# BTTC.net
KiCad netlist of a schematic drawn in Altium Designer
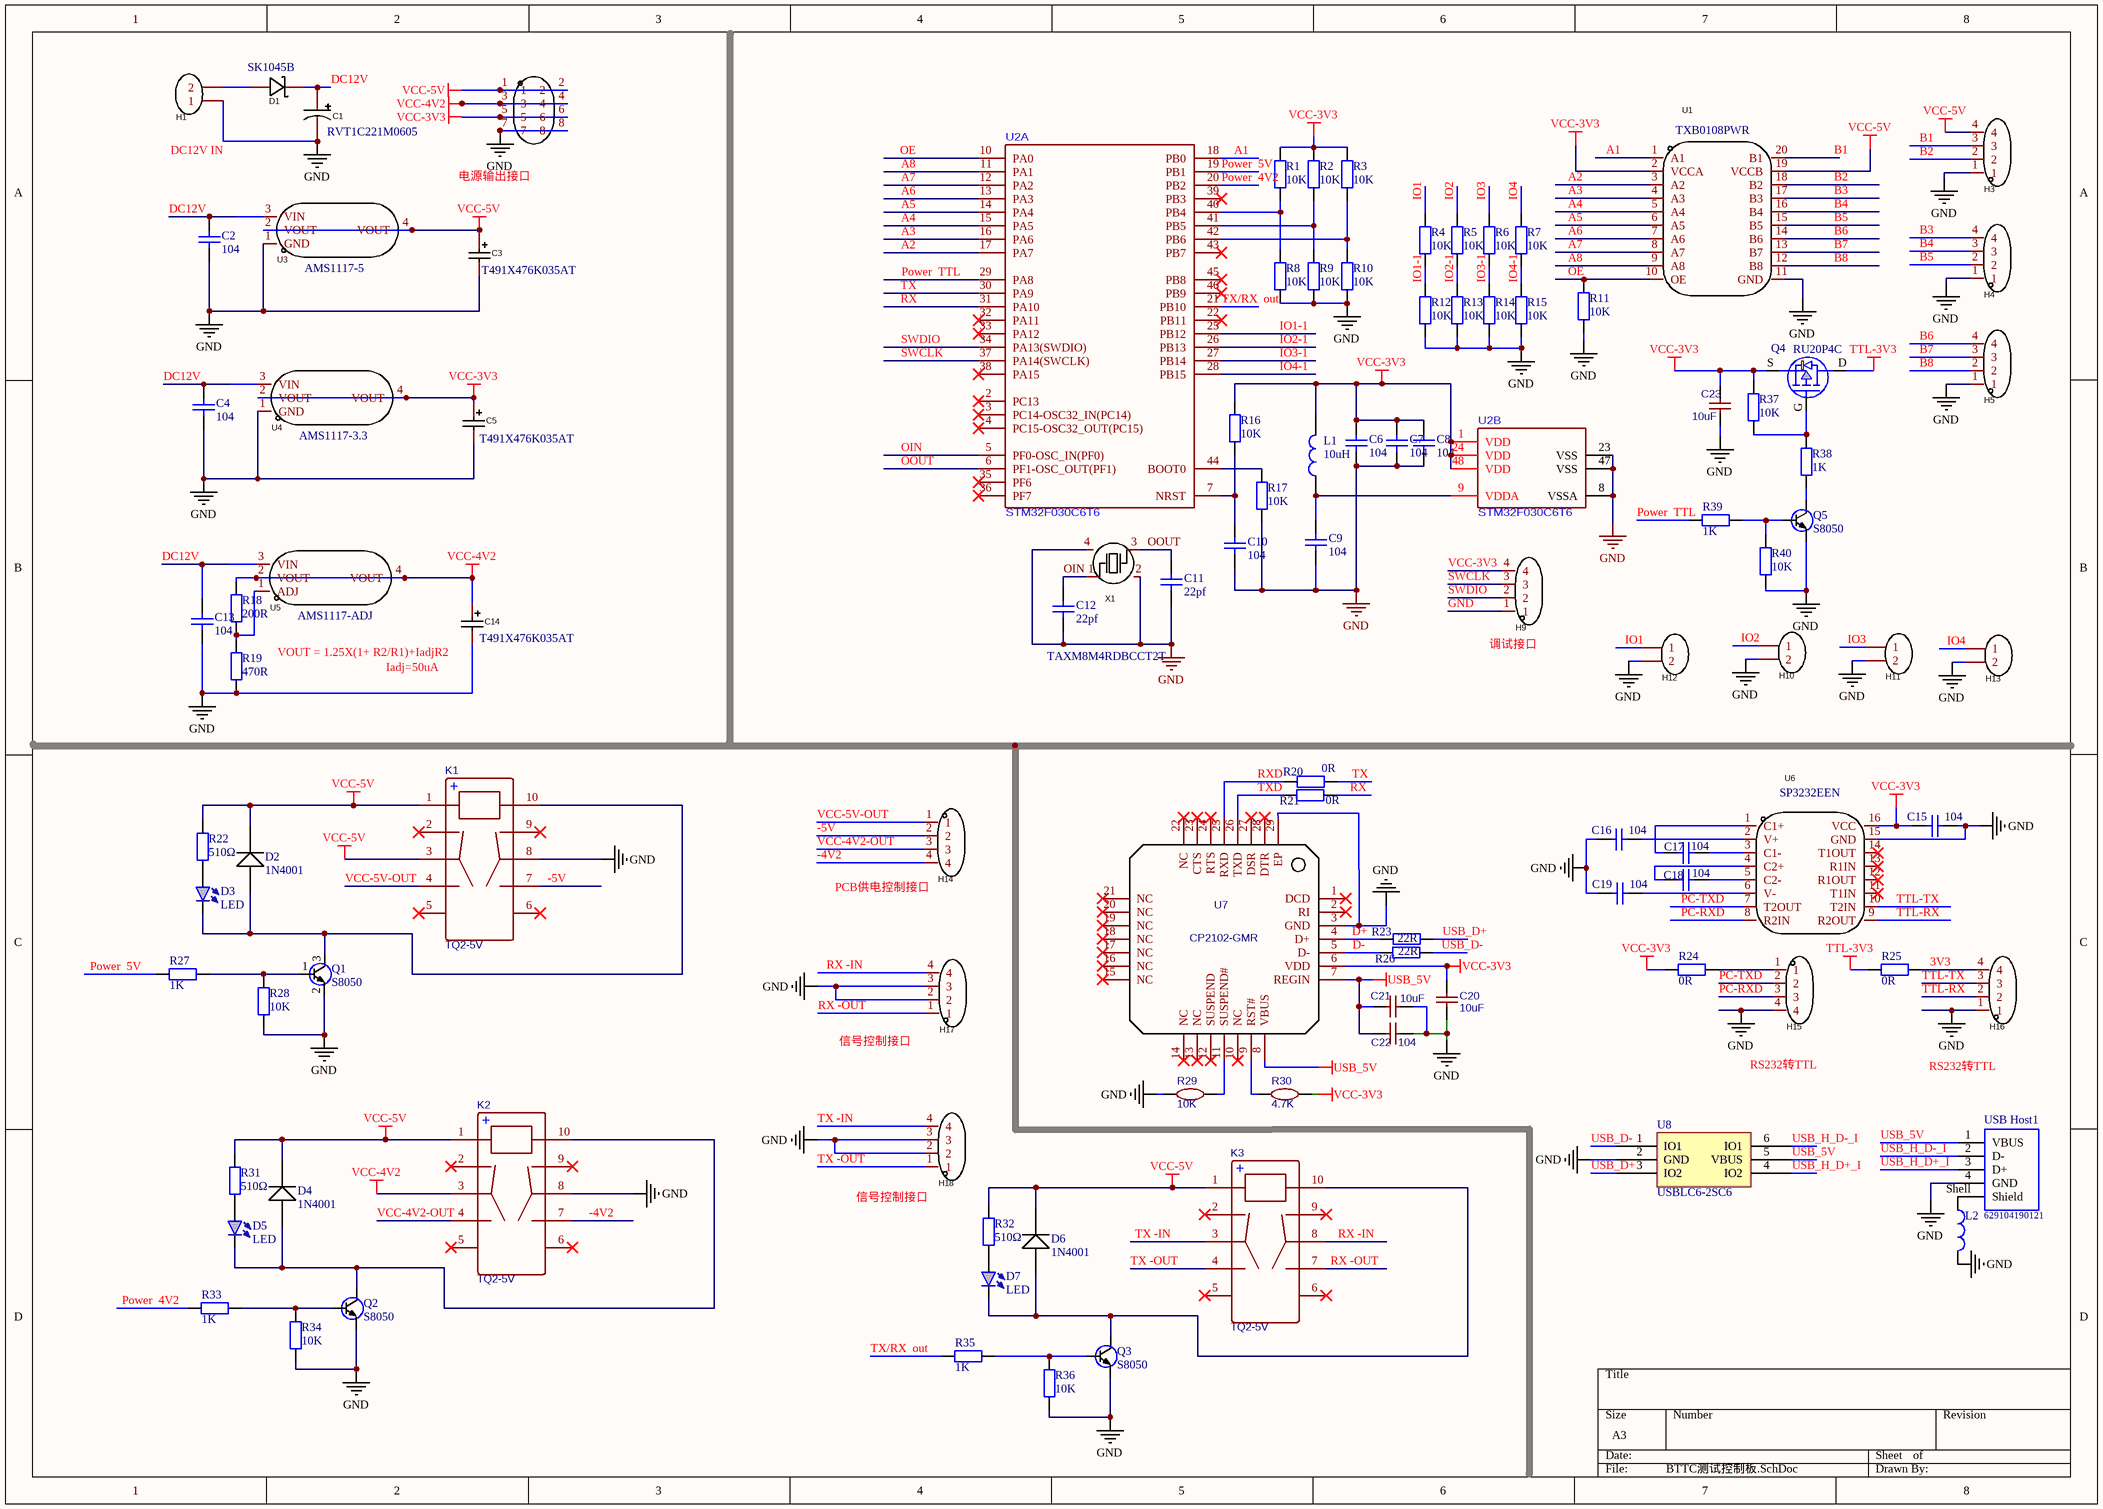
[diagram p0: BTTC测试控制板.SchDoc]

(export (version "E")
  (design (tool "Eeschema 10.0.6"))
  (components
    (comp (ref "C1")
      (value "RVT1C221M0605")
      (footprint "CAP-SMD_BD10.0-L10.3-W10.3-LS11.0-FD")
      (fields (field (name "MANUFACTURER") "ROQANG(容强)") (field (name "TOLERANCE") "±20%"))
      (libsource (lib "SNOWFLAKEV1.0") (part "RVT1C221M0605"))
    )
    (comp (ref "C2") (value "104") (footprint "C0603") (libsource (lib "SNOWFLAKEV1.0") (part "CAP")))
    (comp (ref "C3")
      (value "T491X476K035AT")
      (footprint "CAP-SMD_L3.5-W2.8-R-RD")
      (libsource (lib "altium-import") (part "root_3_T491X476K035AT_"))
    )
    (comp (ref "C4") (value "104") (footprint "C0603") (libsource (lib "SNOWFLAKEV1.0") (part "CAP")))
    (comp (ref "C5")
      (value "T491X476K035AT")
      (footprint "CAP-SMD_L3.5-W2.8-R-RD")
      (libsource (lib "altium-import") (part "root_3_T491X476K035AT_"))
    )
    (comp (ref "C6") (value "104") (footprint "C0603") (libsource (lib "SNOWFLAKEV1.0") (part "CAP")))
    (comp (ref "C7") (value "104") (footprint "C0603") (libsource (lib "SNOWFLAKEV1.0") (part "CAP")))
    (comp (ref "C8") (value "104") (footprint "C0603") (libsource (lib "SNOWFLAKEV1.0") (part "CAP")))
    (comp (ref "C9") (value "104") (footprint "C0603") (libsource (lib "SNOWFLAKEV1.0") (part "CAP")))
    (comp (ref "C10") (value "104") (footprint "C0603") (libsource (lib "SNOWFLAKEV1.0") (part "CAP")))
    (comp (ref "C11") (value "22pf") (footprint "C0603") (libsource (lib "SNOWFLAKEV1.0") (part "CAP")))
    (comp (ref "C12") (value "22pf") (footprint "C0603") (libsource (lib "SNOWFLAKEV1.0") (part "CAP")))
    (comp (ref "C13") (value "104") (footprint "C0603") (libsource (lib "SNOWFLAKEV1.0") (part "CAP")))
    (comp (ref "C14")
      (value "T491X476K035AT")
      (footprint "CAP-SMD_L3.5-W2.8-R-RD")
      (libsource (lib "altium-import") (part "root_3_T491X476K035AT_"))
    )
    (comp (ref "C15") (value "104") (footprint "C0603") (libsource (lib "SNOWFLAKEV1.0") (part "CAP")))
    (comp (ref "C16") (value "104") (footprint "C0603") (libsource (lib "SNOWFLAKEV1.0") (part "CAP")))
    (comp (ref "C17") (value "104") (footprint "C0603") (libsource (lib "SNOWFLAKEV1.0") (part "CAP")))
    (comp (ref "C18") (value "104") (footprint "C0603") (libsource (lib "SNOWFLAKEV1.0") (part "CAP")))
    (comp (ref "C19") (value "104") (footprint "C0603") (libsource (lib "SNOWFLAKEV1.0") (part "CAP")))
    (comp (ref "C20")
      (value "10uF")
      (footprint "C0603")
      (fields
        (field (name "BOM_MANUFACTURER PART") "0603X106K100NT")
        (field (name "BOM_SUPPLIER PART") "C38898")
      )
      (libsource (lib "altium-import") (part "root_1_mirrored_10uF_"))
    )
    (comp (ref "C21")
      (value "10uF")
      (footprint "C0603")
      (fields
        (field (name "BOM_MANUFACTURER PART") "0603X106K100NT")
        (field (name "BOM_SUPPLIER PART") "C38898")
      )
      (libsource (lib "altium-import") (part "root_2_mirrored_10uF_"))
    )
    (comp (ref "C22")
      (value "104")
      (footprint "C0603")
      (fields
        (field (name "BOM_MANUFACTURER PART") "0603B104K500NT")
        (field (name "BOM_SUPPLIER PART") "C30926")
      )
      (libsource (lib "altium-import") (part "root_2_mirrored_100nF_"))
    )
    (comp (ref "C23")
      (value "10uF")
      (footprint "C0603")
      (fields
        (field (name "BOM_MANUFACTURER PART") "0603X106K100NT")
        (field (name "BOM_SUPPLIER PART") "C38898")
      )
      (libsource (lib "altium-import") (part "root_3_mirrored_10uF_"))
    )
    (comp (ref "D1")
      (value "SK1045B")
      (footprint "SMB_L4.6-W3.6-LS5.3-RD")
      (fields (field (name "MANUFACTURER") "MDD"))
      (libsource (lib "SNOWFLAKEV1.0") (part "SK1045B"))
    )
    (comp (ref "D2")
      (value "1N4001")
      (footprint "SMB_L4.6-W3.6-LS5.3-RD")
      (libsource (lib "Schlib2") (part "D"))
    )
    (comp (ref "D3")
      (value "LED")
      (footprint "LED_0603")
      (description "贴片电阻")
      (libsource (lib "SelfbulitSCH_library") (part "LED"))
    )
    (comp (ref "D4")
      (value "1N4001")
      (footprint "SMB_L4.6-W3.6-LS5.3-RD")
      (libsource (lib "Schlib2") (part "D"))
    )
    (comp (ref "D5")
      (value "LED")
      (footprint "LED_0603")
      (description "贴片电阻")
      (libsource (lib "SelfbulitSCH_library") (part "LED"))
    )
    (comp (ref "D6")
      (value "1N4001")
      (footprint "SMB_L4.6-W3.6-LS5.3-RD")
      (libsource (lib "Schlib2") (part "D"))
    )
    (comp (ref "D7")
      (value "LED")
      (footprint "LED_0603")
      (description "贴片电阻")
      (libsource (lib "SelfbulitSCH_library") (part "LED"))
    )
    (comp (ref "H1")
      (value "2P")
      (footprint "CONN-TH_2P-P2.54")
      (fields
        (field (name "MANUFACTURER") "TE Connectivity(美国泰科)")
        (field (name "MANUFACTURER PART") "826629-2")
      )
      (libsource (lib "BTT测试控制板") (part "2P"))
    )
    (comp (ref "H2")
      (value "8p-2.54")
      (footprint "P2.54-4X2")
      (fields
        (field (name "MANUFACTURER") "TE Connectivity(美国泰科)")
        (field (name "MANUFACTURER PART") "826629-4")
      )
      (libsource (lib "BTT测试控制板") (part "8p-2.54"))
    )
    (comp (ref "H3")
      (value "4p-2.54")
      (footprint "CONN-TH_4P-P2.54")
      (fields
        (field (name "MANUFACTURER") "TE Connectivity(美国泰科)")
        (field (name "MANUFACTURER PART") "826629-4")
      )
      (libsource (lib "SNOWFLAKEV1.0") (part "4p-2.54"))
    )
    (comp (ref "H4")
      (value "4p-2.54")
      (footprint "CONN-TH_4P-P2.54")
      (fields
        (field (name "MANUFACTURER") "TE Connectivity(美国泰科)")
        (field (name "MANUFACTURER PART") "826629-4")
      )
      (libsource (lib "SNOWFLAKEV1.0") (part "4p-2.54"))
    )
    (comp (ref "H5")
      (value "4p-2.54")
      (footprint "CONN-TH_4P-P2.54")
      (fields
        (field (name "MANUFACTURER") "TE Connectivity(美国泰科)")
        (field (name "MANUFACTURER PART") "826629-4")
      )
      (libsource (lib "SNOWFLAKEV1.0") (part "4p-2.54"))
    )
    (comp (ref "H9")
      (value "4p-2.54")
      (footprint "CONN-TH_4P-P2.54")
      (fields
        (field (name "MANUFACTURER") "TE Connectivity(美国泰科)")
        (field (name "MANUFACTURER PART") "826629-4")
      )
      (libsource (lib "SNOWFLAKEV1.0") (part "4p-2.54"))
    )
    (comp (ref "H10")
      (value "2P")
      (footprint "CONN-TH_2P-P2.54")
      (fields
        (field (name "MANUFACTURER") "TE Connectivity(美国泰科)")
        (field (name "MANUFACTURER PART") "826629-2")
      )
      (libsource (lib "BTT测试控制板") (part "2P"))
    )
    (comp (ref "H11")
      (value "2P")
      (footprint "CONN-TH_2P-P2.54")
      (fields
        (field (name "MANUFACTURER") "TE Connectivity(美国泰科)")
        (field (name "MANUFACTURER PART") "826629-2")
      )
      (libsource (lib "BTT测试控制板") (part "2P"))
    )
    (comp (ref "H12")
      (value "2P")
      (footprint "CONN-TH_2P-P2.54")
      (fields
        (field (name "MANUFACTURER") "TE Connectivity(美国泰科)")
        (field (name "MANUFACTURER PART") "826629-2")
      )
      (libsource (lib "BTT测试控制板") (part "2P"))
    )
    (comp (ref "H13")
      (value "2P")
      (footprint "CONN-TH_2P-P2.54")
      (fields
        (field (name "MANUFACTURER") "TE Connectivity(美国泰科)")
        (field (name "MANUFACTURER PART") "826629-2")
      )
      (libsource (lib "BTT测试控制板") (part "2P"))
    )
    (comp (ref "H14")
      (value "4p-2.54")
      (footprint "CONN-TH_4P-P2.54")
      (fields
        (field (name "MANUFACTURER") "TE Connectivity(美国泰科)")
        (field (name "MANUFACTURER PART") "826629-4")
      )
      (libsource (lib "SNOWFLAKEV1.0") (part "4p-2.54"))
    )
    (comp (ref "H15")
      (value "4p-2.54")
      (footprint "CONN-TH_4P-P2.54")
      (fields
        (field (name "MANUFACTURER") "TE Connectivity(美国泰科)")
        (field (name "MANUFACTURER PART") "826629-4")
      )
      (libsource (lib "SNOWFLAKEV1.0") (part "4p-2.54"))
    )
    (comp (ref "H16")
      (value "4p-2.54")
      (footprint "CONN-TH_4P-P2.54")
      (fields
        (field (name "MANUFACTURER") "TE Connectivity(美国泰科)")
        (field (name "MANUFACTURER PART") "826629-4")
      )
      (libsource (lib "SNOWFLAKEV1.0") (part "4p-2.54"))
    )
    (comp (ref "H17")
      (value "4p-2.54")
      (footprint "CONN-TH_4P-P2.54")
      (fields
        (field (name "MANUFACTURER") "TE Connectivity(美国泰科)")
        (field (name "MANUFACTURER PART") "826629-4")
      )
      (libsource (lib "SNOWFLAKEV1.0") (part "4p-2.54"))
    )
    (comp (ref "H18")
      (value "4p-2.54")
      (footprint "CONN-TH_4P-P2.54")
      (fields
        (field (name "MANUFACTURER") "TE Connectivity(美国泰科)")
        (field (name "MANUFACTURER PART") "826629-4")
      )
      (libsource (lib "SNOWFLAKEV1.0") (part "4p-2.54"))
    )
    (comp (ref "K1")
      (value "TQ2-5V")
      (footprint "RELAY-TH_TQ2-XXV")
      (fields (field (name "BOM_SUPPLIER PART") "C46047"))
      (libsource (lib "SelfbulitSCH_library") (part "TQ2-5V"))
    )
    (comp (ref "K2")
      (value "TQ2-5V")
      (footprint "RELAY-TH_TQ2-XXV")
      (fields (field (name "BOM_SUPPLIER PART") "C46047"))
      (libsource (lib "SelfbulitSCH_library") (part "TQ2-5V"))
    )
    (comp (ref "K3")
      (value "TQ2-5V")
      (footprint "RELAY-TH_TQ2-XXV")
      (fields (field (name "BOM_SUPPLIER PART") "C46047"))
      (libsource (lib "SelfbulitSCH_library") (part "TQ2-5V"))
    )
    (comp (ref "L1") (value "10uH") (footprint "L0603") (libsource (lib "SNOWFLAKEV1.0") (part "L")))
    (comp (ref "L2")
      (value "PZ1608D121-2R0TF")
      (footprint "L0603")
      (libsource (lib "Halry Altium Server") (part "Inductor"))
    )
    (comp (ref "Q1") (value "S8050") (footprint "SOT23-3") (libsource (lib "") (part "S8050_2")))
    (comp (ref "Q2")
      (value "S8050")
      (footprint "SOT23-3")
      (libsource (lib "SelfbulitSCH_library") (part "S8050"))
    )
    (comp (ref "Q3") (value "S8050") (footprint "SOT23-3") (libsource (lib "") (part "S8050_1")))
    (comp (ref "Q4") (value "RU20P4C") (footprint "SOT23-M") (libsource (lib "*") (part "P-MOS")))
    (comp (ref "Q5") (value "S8050") (footprint "SOT23-3") (libsource (lib "") (part "S8050_3")))
    (comp (ref "R1")
      (value "10K")
      (footprint "R0603")
      (description "Resistor")
      (fields (field (name "PUBLISHER") "Altium Limited"))
      (libsource (lib "SNOWFLAKEV1.0") (part "Res"))
    )
    (comp (ref "R2")
      (value "10K")
      (footprint "R0603")
      (description "Resistor")
      (fields (field (name "PUBLISHER") "Altium Limited"))
      (libsource (lib "SNOWFLAKEV1.0") (part "Res"))
    )
    (comp (ref "R3")
      (value "10K")
      (footprint "R0603")
      (description "Resistor")
      (fields (field (name "PUBLISHER") "Altium Limited"))
      (libsource (lib "SNOWFLAKEV1.0") (part "Res"))
    )
    (comp (ref "R4")
      (value "10K")
      (footprint "R0603")
      (description "Resistor")
      (fields (field (name "PUBLISHER") "Altium Limited"))
      (libsource (lib "SNOWFLAKEV1.0") (part "Res"))
    )
    (comp (ref "R5")
      (value "10K")
      (footprint "R0603")
      (description "Resistor")
      (fields (field (name "PUBLISHER") "Altium Limited"))
      (libsource (lib "SNOWFLAKEV1.0") (part "Res"))
    )
    (comp (ref "R6")
      (value "10K")
      (footprint "R0603")
      (description "Resistor")
      (fields (field (name "PUBLISHER") "Altium Limited"))
      (libsource (lib "SNOWFLAKEV1.0") (part "Res"))
    )
    (comp (ref "R7")
      (value "10K")
      (footprint "R0603")
      (description "Resistor")
      (fields (field (name "PUBLISHER") "Altium Limited"))
      (libsource (lib "SNOWFLAKEV1.0") (part "Res"))
    )
    (comp (ref "R8")
      (value "10K")
      (footprint "R0603")
      (description "Resistor")
      (fields (field (name "PUBLISHER") "Altium Limited"))
      (libsource (lib "SNOWFLAKEV1.0") (part "Res"))
    )
    (comp (ref "R9")
      (value "10K")
      (footprint "R0603")
      (description "Resistor")
      (fields (field (name "PUBLISHER") "Altium Limited"))
      (libsource (lib "SNOWFLAKEV1.0") (part "Res"))
    )
    (comp (ref "R10")
      (value "10K")
      (footprint "R0603")
      (description "Resistor")
      (fields (field (name "PUBLISHER") "Altium Limited"))
      (libsource (lib "SNOWFLAKEV1.0") (part "Res"))
    )
    (comp (ref "R11")
      (value "10K")
      (footprint "R0603")
      (description "Resistor")
      (fields (field (name "PUBLISHER") "Altium Limited"))
      (libsource (lib "SNOWFLAKEV1.0") (part "Res"))
    )
    (comp (ref "R12")
      (value "10K")
      (footprint "R0603")
      (description "Resistor")
      (fields (field (name "PUBLISHER") "Altium Limited"))
      (libsource (lib "SNOWFLAKEV1.0") (part "Res"))
    )
    (comp (ref "R13")
      (value "10K")
      (footprint "R0603")
      (description "Resistor")
      (fields (field (name "PUBLISHER") "Altium Limited"))
      (libsource (lib "SNOWFLAKEV1.0") (part "Res"))
    )
    (comp (ref "R14")
      (value "10K")
      (footprint "R0603")
      (description "Resistor")
      (fields (field (name "PUBLISHER") "Altium Limited"))
      (libsource (lib "SNOWFLAKEV1.0") (part "Res"))
    )
    (comp (ref "R15")
      (value "10K")
      (footprint "R0603")
      (description "Resistor")
      (fields (field (name "PUBLISHER") "Altium Limited"))
      (libsource (lib "SNOWFLAKEV1.0") (part "Res"))
    )
    (comp (ref "R16")
      (value "10K")
      (footprint "R0603")
      (description "Resistor")
      (fields (field (name "PUBLISHER") "Altium Limited"))
      (libsource (lib "SNOWFLAKEV1.0") (part "Res"))
    )
    (comp (ref "R17")
      (value "10K")
      (footprint "R0603")
      (description "Resistor")
      (fields (field (name "PUBLISHER") "Altium Limited"))
      (libsource (lib "SNOWFLAKEV1.0") (part "Res"))
    )
    (comp (ref "R18")
      (value "200R")
      (footprint "R0603")
      (description "Resistor")
      (fields (field (name "PUBLISHER") "Altium Limited"))
      (libsource (lib "SNOWFLAKEV1.0") (part "Res"))
    )
    (comp (ref "R19")
      (value "470R")
      (footprint "R0603")
      (description "Resistor")
      (fields (field (name "PUBLISHER") "Altium Limited"))
      (libsource (lib "SNOWFLAKEV1.0") (part "Res"))
    )
    (comp (ref "R20")
      (value "0R")
      (footprint "R0603")
      (description "贴片电阻")
      (libsource (lib "Miscellaneous Devices LC") (part "0603 10KΩ (1002) 1%"))
    )
    (comp (ref "R21")
      (value "0R")
      (footprint "R0603")
      (description "贴片电阻")
      (libsource (lib "Miscellaneous Devices LC") (part "0603 10KΩ (1002) 1%"))
    )
    (comp (ref "R22")
      (value "510Ω")
      (footprint "R0603")
      (description "贴片电阻")
      (libsource (lib "Miscellaneous Devices LC") (part "0603 510Ω (5100) 1%"))
    )
    (comp (ref "R23")
      (value "22R")
      (footprint "R0603")
      (description "贴片电阻")
      (libsource (lib "Miscellaneous Devices LC") (part "0603 10KΩ (1002) 1%"))
    )
    (comp (ref "R24")
      (value "0R")
      (footprint "R0603")
      (description "贴片电阻")
      (libsource (lib "Miscellaneous Devices LC") (part "0603 1KΩ (1001) 1%"))
    )
    (comp (ref "R25")
      (value "0R")
      (footprint "R0603")
      (description "贴片电阻")
      (libsource (lib "Miscellaneous Devices LC") (part "0603 1KΩ (1001) 1%"))
    )
    (comp (ref "R26")
      (value "22R")
      (footprint "R0603")
      (description "贴片电阻")
      (libsource (lib "Miscellaneous Devices LC") (part "0603 10KΩ (1002) 1%"))
    )
    (comp (ref "R27")
      (value "1K")
      (footprint "R0603")
      (description "贴片电阻")
      (libsource (lib "Miscellaneous Devices LC") (part "0603 1KΩ (1001) 1%"))
    )
    (comp (ref "R28")
      (value "10K")
      (footprint "R0603")
      (description "贴片电阻")
      (libsource (lib "") (part "0603 10KΩ (1002) 1%_1"))
    )
    (comp (ref "R29")
      (value "10K")
      (footprint "R0603")
      (fields
        (field (name "BOM_MANUFACTURER PART") "0603WAF1002T5E")
        (field (name "BOM_SUPPLIER PART") "C25804")
      )
      (libsource (lib "altium-import") (part "root_2_mirrored_10K_"))
    )
    (comp (ref "R30")
      (value "4.7K")
      (footprint "R0603")
      (fields
        (field (name "BOM_MANUFACTURER PART") "0603WAJ0472T5E")
        (field (name "BOM_SUPPLIER PART") "C25999")
      )
      (libsource (lib "altium-import") (part "root_0_mirrored_4.7K_"))
    )
    (comp (ref "R31")
      (value "510Ω")
      (footprint "R0603")
      (description "贴片电阻")
      (libsource (lib "Miscellaneous Devices LC") (part "0603 510Ω (5100) 1%"))
    )
    (comp (ref "R32")
      (value "510Ω")
      (footprint "R0603")
      (description "贴片电阻")
      (libsource (lib "Miscellaneous Devices LC") (part "0603 510Ω (5100) 1%"))
    )
    (comp (ref "R33")
      (value "1K")
      (footprint "R0603")
      (description "贴片电阻")
      (libsource (lib "Miscellaneous Devices LC") (part "0603 1KΩ (1001) 1%"))
    )
    (comp (ref "R34")
      (value "10K")
      (footprint "R0603")
      (description "贴片电阻")
      (libsource (lib "") (part "0603 10KΩ (1002) 1%_1"))
    )
    (comp (ref "R35")
      (value "1K")
      (footprint "R0603")
      (description "贴片电阻")
      (libsource (lib "Miscellaneous Devices LC") (part "0603 1KΩ (1001) 1%"))
    )
    (comp (ref "R36")
      (value "10K")
      (footprint "R0603")
      (description "贴片电阻")
      (libsource (lib "") (part "0603 10KΩ (1002) 1%_1"))
    )
    (comp (ref "R37")
      (value "10K")
      (footprint "R0603")
      (description "Resistor")
      (fields (field (name "PUBLISHER") "Altium Limited"))
      (libsource (lib "SNOWFLAKEV1.0") (part "Res"))
    )
    (comp (ref "R38")
      (value "1K")
      (footprint "R0603")
      (description "Resistor")
      (fields (field (name "PUBLISHER") "Altium Limited"))
      (libsource (lib "SNOWFLAKEV1.0") (part "Res"))
    )
    (comp (ref "R39")
      (value "1K")
      (footprint "R0603")
      (description "贴片电阻")
      (libsource (lib "Miscellaneous Devices LC") (part "0603 1KΩ (1001) 1%"))
    )
    (comp (ref "R40")
      (value "10K")
      (footprint "R0603")
      (description "贴片电阻")
      (libsource (lib "") (part "0603 10KΩ (1002) 1%_1"))
    )
    (comp (ref "U1")
      (value "TXB0108PWR")
      (footprint "TSSOP-20")
      (libsource (lib "altium-import") (part "root_0_TXB0108PWR_"))
    )
    (comp (ref "U2")
      (value "STM32F030C6T6")
      (footprint "LQFP-48_7x7x05P")
      (libsource (lib "SNOWFLAKEV1.0") (part "STM32F030C6T6"))
    )
    (comp (ref "U3")
      (value "AMS1117-5")
      (footprint "SOT-223")
      (fields
        (field (name "MANUFACTURER") "I-CORE(中微爱芯)")
        (field (name "MANUFACTURER PART") "AIP1117-5GH.TR")
      )
      (libsource (lib "SNOWFLAKEV1.0") (part "AIP1117-5GH.TR"))
    )
    (comp (ref "U4")
      (value "AMS1117-3.3")
      (footprint "SOT-223")
      (fields
        (field (name "MANUFACTURER") "I-CORE(中微爱芯)")
        (field (name "MANUFACTURER PART") "AIP1117-5GH.TR")
      )
      (libsource (lib "SNOWFLAKEV1.0") (part "AIP1117-5GH.TR"))
    )
    (comp (ref "U5")
      (value "AMS1117-ADJ")
      (footprint "SOT-223")
      (fields
        (field (name "MANUFACTURER") "I-CORE(中微爱芯)")
        (field (name "MANUFACTURER PART") "AIP1117-5GH.TR")
      )
      (libsource (lib "SNOWFLAKEV1.0") (part "AIP1117-5GH.TR"))
    )
    (comp (ref "U6")
      (value "SP3232EEN")
      (footprint "SOP-16_L10.0-W3.9-P1.27-LS6.0-BL")
      (libsource (lib "altium-import") (part "root_0_SP3232EEN_"))
    )
    (comp (ref "U7")
      (value "CP2102-GMR")
      (footprint "WQFN-28_L5.0-W5.0-P0.50-BL-EP3.2")
      (fields (field (name "BOM_SUPPLIER PART") "C6568"))
      (libsource (lib "altium-import") (part "root_0_mirrored_CP2102-GMR_"))
    )
    (comp (ref "U8")
      (value "USBLC6-2SC6")
      (footprint "SOT-23-6_L2.9-W1.6-P0.95-LS2.8-BR")
      (description "TVS DIODE 5.25V 17V SOT23-6")
      (libsource (lib "Halry Altium Server") (part "USBLC6-2SC6"))
    )
    (comp (ref "USB Host1")
      (value "629104190121")
      (footprint "USB-A")
      (description "USB 2.0 Type A, Receptacle, Horizontal - Short Type, SMT")
      (fields (field (name "MANUFACTURER") "Wurth Elektronik"))
      (libsource (lib "Halry Altium Server") (part "Symbol"))
    )
    (comp (ref "X1")
      (value "TAXM8M4RDBCCT2T")
      (footprint "OSC-SMD_4P-L3.2-W2.5-BL")
      (fields (field (name "MANUFACTURER") "TAE(雅晶鑫)"))
      (libsource (lib "SNOWFLAKEV1.0") (part "TAXM8M4RDBCCT2T"))
    )
  )
  (nets
    (net (code "1") (name "/-4V2") (class "Default")
      (node (ref "H14") (pin "4") (pinfunction "4_4") (pintype "passive"))
      (node (ref "K2") (pin "7") (pinfunction "7_7") (pintype "passive"))
    )
    (net (code "2") (name "/-5V") (class "Default")
      (node (ref "H14") (pin "2") (pinfunction "2_2") (pintype "passive"))
      (node (ref "K1") (pin "7") (pinfunction "7_7") (pintype "passive"))
    )
    (net (code "3") (name "/3V3") (class "Default")
      (node (ref "H16") (pin "4") (pinfunction "4_4") (pintype "passive"))
      (node (ref "R25") (pin "1") (pinfunction "1_1") (pintype "passive"))
    )
    (net (code "4") (name "/A1") (class "Default")
      (node (ref "U1") (pin "1") (pinfunction "A1_1") (pintype "passive"))
      (node (ref "U2") (pin "18") (pinfunction "PB0_18") (pintype "passive"))
    )
    (net (code "5") (name "/A2") (class "Default")
      (node (ref "U1") (pin "3") (pinfunction "A2_3") (pintype "passive"))
      (node (ref "U2") (pin "17") (pinfunction "PA7_17") (pintype "passive"))
    )
    (net (code "6") (name "/A3") (class "Default")
      (node (ref "U1") (pin "4") (pinfunction "A3_4") (pintype "passive"))
      (node (ref "U2") (pin "16") (pinfunction "PA6_16") (pintype "passive"))
    )
    (net (code "7") (name "/A4") (class "Default")
      (node (ref "U1") (pin "5") (pinfunction "A4_5") (pintype "passive"))
      (node (ref "U2") (pin "15") (pinfunction "PA5_15") (pintype "passive"))
    )
    (net (code "8") (name "/A5") (class "Default")
      (node (ref "U1") (pin "6") (pinfunction "A5_6") (pintype "passive"))
      (node (ref "U2") (pin "14") (pinfunction "PA4_14") (pintype "passive"))
    )
    (net (code "9") (name "/A6") (class "Default")
      (node (ref "U1") (pin "7") (pinfunction "A6_7") (pintype "passive"))
      (node (ref "U2") (pin "13") (pinfunction "PA3_13") (pintype "passive"))
    )
    (net (code "10") (name "/A7") (class "Default")
      (node (ref "U1") (pin "8") (pinfunction "A7_8") (pintype "passive"))
      (node (ref "U2") (pin "12") (pinfunction "PA2_12") (pintype "passive"))
    )
    (net (code "11") (name "/A8") (class "Default")
      (node (ref "U1") (pin "9") (pinfunction "A8_9") (pintype "passive"))
      (node (ref "U2") (pin "11") (pinfunction "PA1_11") (pintype "passive"))
    )
    (net (code "12") (name "/B1") (class "Default")
      (node (ref "H3") (pin "3") (pinfunction "3_3") (pintype "passive"))
      (node (ref "U1") (pin "20") (pinfunction "B1_20") (pintype "passive"))
    )
    (net (code "13") (name "/B2") (class "Default")
      (node (ref "H3") (pin "2") (pinfunction "2_2") (pintype "passive"))
      (node (ref "U1") (pin "18") (pinfunction "B2_18") (pintype "passive"))
    )
    (net (code "14") (name "/B3") (class "Default")
      (node (ref "H4") (pin "4") (pinfunction "4_4") (pintype "passive"))
      (node (ref "U1") (pin "17") (pinfunction "B3_17") (pintype "passive"))
    )
    (net (code "15") (name "/B4") (class "Default")
      (node (ref "H4") (pin "3") (pinfunction "3_3") (pintype "passive"))
      (node (ref "U1") (pin "16") (pinfunction "B4_16") (pintype "passive"))
    )
    (net (code "16") (name "/B5") (class "Default")
      (node (ref "H4") (pin "2") (pinfunction "2_2") (pintype "passive"))
      (node (ref "U1") (pin "15") (pinfunction "B5_15") (pintype "passive"))
    )
    (net (code "17") (name "/B6") (class "Default")
      (node (ref "H5") (pin "4") (pinfunction "4_4") (pintype "passive"))
      (node (ref "U1") (pin "14") (pinfunction "B6_14") (pintype "passive"))
    )
    (net (code "18") (name "/B7") (class "Default")
      (node (ref "H5") (pin "3") (pinfunction "3_3") (pintype "passive"))
      (node (ref "U1") (pin "13") (pinfunction "B7_13") (pintype "passive"))
    )
    (net (code "19") (name "/B8") (class "Default")
      (node (ref "H5") (pin "2") (pinfunction "2_2") (pintype "passive"))
      (node (ref "U1") (pin "12") (pinfunction "B8_12") (pintype "passive"))
    )
    (net (code "20") (name "/D+") (class "Default")
      (node (ref "R23") (pin "2") (pinfunction "2_2") (pintype "passive"))
      (node (ref "U7") (pin "4") (pinfunction "D+_4") (pintype "passive"))
    )
    (net (code "21") (name "/D-") (class "Default")
      (node (ref "R26") (pin "2") (pinfunction "2_2") (pintype "passive"))
      (node (ref "U7") (pin "5") (pinfunction "D-_5") (pintype "passive"))
    )
    (net (code "22") (name "/DC12V") (class "Default")
      (node (ref "C1") (pin "1") (pinfunction "1_1") (pintype "passive"))
      (node (ref "C13") (pin "1") (pinfunction "1_1") (pintype "passive"))
      (node (ref "C2") (pin "1") (pinfunction "1_1") (pintype "passive"))
      (node (ref "C4") (pin "1") (pinfunction "1_1") (pintype "passive"))
      (node (ref "D1") (pin "1") (pinfunction "K_1") (pintype "passive"))
      (node (ref "U3") (pin "3") (pinfunction "VIN_3") (pintype "passive"))
      (node (ref "U4") (pin "3") (pinfunction "VIN_3") (pintype "passive"))
      (node (ref "U5") (pin "3") (pinfunction "VIN_3") (pintype "passive"))
    )
    (net (code "23") (name "/IO1") (class "Default")
      (node (ref "H12") (pin "1") (pinfunction "1_1") (pintype "passive"))
      (node (ref "R4") (pin "1") (pinfunction "1_1") (pintype "passive"))
    )
    (net (code "24") (name "/IO1-1") (class "Default")
      (node (ref "R12") (pin "1") (pinfunction "1_1") (pintype "passive"))
      (node (ref "R4") (pin "2") (pinfunction "2_2") (pintype "passive"))
      (node (ref "U2") (pin "25") (pinfunction "PB12_25") (pintype "passive"))
    )
    (net (code "25") (name "/IO2") (class "Default")
      (node (ref "H10") (pin "1") (pinfunction "1_1") (pintype "passive"))
      (node (ref "R5") (pin "1") (pinfunction "1_1") (pintype "passive"))
    )
    (net (code "26") (name "/IO2-1") (class "Default")
      (node (ref "R13") (pin "1") (pinfunction "1_1") (pintype "passive"))
      (node (ref "R5") (pin "2") (pinfunction "2_2") (pintype "passive"))
      (node (ref "U2") (pin "26") (pinfunction "PB13_26") (pintype "passive"))
    )
    (net (code "27") (name "/IO3") (class "Default")
      (node (ref "H11") (pin "1") (pinfunction "1_1") (pintype "passive"))
      (node (ref "R6") (pin "1") (pinfunction "1_1") (pintype "passive"))
    )
    (net (code "28") (name "/IO3-1") (class "Default")
      (node (ref "R14") (pin "1") (pinfunction "1_1") (pintype "passive"))
      (node (ref "R6") (pin "2") (pinfunction "2_2") (pintype "passive"))
      (node (ref "U2") (pin "27") (pinfunction "PB14_27") (pintype "passive"))
    )
    (net (code "29") (name "/IO4") (class "Default")
      (node (ref "H13") (pin "1") (pinfunction "1_1") (pintype "passive"))
      (node (ref "R7") (pin "1") (pinfunction "1_1") (pintype "passive"))
    )
    (net (code "30") (name "/IO4-1") (class "Default")
      (node (ref "R15") (pin "1") (pinfunction "1_1") (pintype "passive"))
      (node (ref "R7") (pin "2") (pinfunction "2_2") (pintype "passive"))
      (node (ref "U2") (pin "28") (pinfunction "PB15_28") (pintype "passive"))
    )
    (net (code "31") (name "/OE") (class "Default")
      (node (ref "R11") (pin "1") (pinfunction "1_1") (pintype "passive"))
      (node (ref "U1") (pin "10") (pinfunction "OE_10") (pintype "passive"))
      (node (ref "U2") (pin "10") (pinfunction "PA0_10") (pintype "passive"))
    )
    (net (code "32") (name "/OIN") (class "Default")
      (node (ref "C12") (pin "1") (pinfunction "1_1") (pintype "passive"))
      (node (ref "U2") (pin "5") (pinfunction "PF0-OSC_IN(PF0)_5") (pintype "passive"))
      (node (ref "X1") (pin "1") (pinfunction "1_1") (pintype "passive"))
    )
    (net (code "33") (name "/OOUT") (class "Default")
      (node (ref "C11") (pin "1") (pinfunction "1_1") (pintype "passive"))
      (node (ref "U2") (pin "6") (pinfunction "PF1-OSC_OUT(PF1)_6") (pintype "passive"))
      (node (ref "X1") (pin "3") (pinfunction "3_3") (pintype "passive"))
    )
    (net (code "34") (name "/PC-RXD") (class "Default")
      (node (ref "H15") (pin "3") (pinfunction "3_3") (pintype "passive"))
      (node (ref "U6") (pin "8") (pinfunction "R2IN_8") (pintype "passive"))
    )
    (net (code "35") (name "/PC-TXD") (class "Default")
      (node (ref "H15") (pin "2") (pinfunction "2_2") (pintype "passive"))
      (node (ref "U6") (pin "7") (pinfunction "T2OUT_7") (pintype "passive"))
    )
    (net (code "36") (name "/Power  4V2") (class "Default")
      (node (ref "R33") (pin "2") (pinfunction "2_2") (pintype "passive"))
      (node (ref "U2") (pin "20") (pinfunction "PB2_20") (pintype "passive"))
    )
    (net (code "37") (name "/Power  5V") (class "Default")
      (node (ref "R27") (pin "2") (pinfunction "2_2") (pintype "passive"))
      (node (ref "U2") (pin "19") (pinfunction "PB1_19") (pintype "passive"))
    )
    (net (code "38") (name "/Power  TTL") (class "Default")
      (node (ref "R39") (pin "2") (pinfunction "2_2") (pintype "passive"))
      (node (ref "U2") (pin "29") (pinfunction "PA8_29") (pintype "passive"))
    )
    (net (code "39") (name "/RX") (class "Default")
      (node (ref "R21") (pin "1") (pinfunction "1_1") (pintype "passive"))
      (node (ref "U2") (pin "31") (pinfunction "PA10_31") (pintype "passive"))
    )
    (net (code "40") (name "/RX -IN") (class "Default")
      (node (ref "H17") (pin "4") (pinfunction "4_4") (pintype "passive"))
      (node (ref "K3") (pin "8") (pinfunction "8_8") (pintype "passive"))
    )
    (net (code "41") (name "/RX -OUT") (class "Default")
      (node (ref "H17") (pin "1") (pinfunction "1_1") (pintype "passive"))
      (node (ref "K3") (pin "7") (pinfunction "7_7") (pintype "passive"))
    )
    (net (code "42") (name "/RXD") (class "Default")
      (node (ref "R20") (pin "2") (pinfunction "2_2") (pintype "passive"))
      (node (ref "U7") (pin "25") (pinfunction "RXD_25") (pintype "passive"))
    )
    (net (code "43") (name "/SWCLK") (class "Default")
      (node (ref "H9") (pin "3") (pinfunction "3_3") (pintype "passive"))
      (node (ref "U2") (pin "37") (pinfunction "PA14(SWCLK)_37") (pintype "passive"))
    )
    (net (code "44") (name "/SWDIO") (class "Default")
      (node (ref "H9") (pin "2") (pinfunction "2_2") (pintype "passive"))
      (node (ref "U2") (pin "34") (pinfunction "PA13(SWDIO)_34") (pintype "passive"))
    )
    (net (code "45") (name "/TTL-RX") (class "Default")
      (node (ref "H16") (pin "2") (pinfunction "2_2") (pintype "passive"))
      (node (ref "U6") (pin "9") (pinfunction "R2OUT_9") (pintype "passive"))
    )
    (net (code "46") (name "/TTL-TX") (class "Default")
      (node (ref "H16") (pin "3") (pinfunction "3_3") (pintype "passive"))
      (node (ref "U6") (pin "10") (pinfunction "T2IN_10") (pintype "passive"))
    )
    (net (code "47") (name "/TX") (class "Default")
      (node (ref "R20") (pin "1") (pinfunction "1_1") (pintype "passive"))
      (node (ref "U2") (pin "30") (pinfunction "PA9_30") (pintype "passive"))
    )
    (net (code "48") (name "/TX -IN") (class "Default")
      (node (ref "H18") (pin "4") (pinfunction "4_4") (pintype "passive"))
      (node (ref "K3") (pin "3") (pinfunction "3_3") (pintype "passive"))
    )
    (net (code "49") (name "/TX -OUT") (class "Default")
      (node (ref "H18") (pin "1") (pinfunction "1_1") (pintype "passive"))
      (node (ref "K3") (pin "4") (pinfunction "4_4") (pintype "passive"))
    )
    (net (code "50") (name "/TXD") (class "Default")
      (node (ref "R21") (pin "2") (pinfunction "2_2") (pintype "passive"))
      (node (ref "U7") (pin "26") (pinfunction "TXD_26") (pintype "passive"))
    )
    (net (code "51") (name "/TX{slash}RX  out") (class "Default")
      (node (ref "R35") (pin "2") (pinfunction "2_2") (pintype "passive"))
      (node (ref "U2") (pin "21") (pinfunction "PB10_21") (pintype "passive"))
    )
    (net (code "52") (name "/USB_D+") (class "Default")
      (node (ref "R23") (pin "1") (pinfunction "1_1") (pintype "passive"))
      (node (ref "U8") (pin "3") (pinfunction "IO2_3") (pintype "passive"))
    )
    (net (code "53") (name "/USB_D-") (class "Default")
      (node (ref "R26") (pin "1") (pinfunction "1_1") (pintype "passive"))
      (node (ref "U8") (pin "1") (pinfunction "IO1_1") (pintype "passive"))
    )
    (net (code "54") (name "/USB_H_D+_I") (class "Default")
      (node (ref "U8") (pin "4") (pinfunction "IO2_4") (pintype "passive"))
      (node (ref "USB Host1") (pin "3") (pinfunction "D+_3") (pintype "passive"))
    )
    (net (code "55") (name "/USB_H_D-_I") (class "Default")
      (node (ref "U8") (pin "6") (pinfunction "IO1_6") (pintype "passive"))
      (node (ref "USB Host1") (pin "2") (pinfunction "D-_2") (pintype "passive"))
    )
    (net (code "56") (name "/VCC-4V2-OUT") (class "Default")
      (node (ref "H14") (pin "3") (pinfunction "3_3") (pintype "passive"))
      (node (ref "K2") (pin "4") (pinfunction "4_4") (pintype "passive"))
    )
    (net (code "57") (name "/VCC-5V-OUT") (class "Default")
      (node (ref "H14") (pin "1") (pinfunction "1_1") (pintype "passive"))
      (node (ref "K1") (pin "4") (pinfunction "4_4") (pintype "passive"))
    )
    (net (code "58") (name "GND") (class "Default")
      (node (ref "C1") (pin "2") (pinfunction "2_2") (pintype "passive"))
      (node (ref "C10") (pin "2") (pinfunction "2_2") (pintype "passive"))
      (node (ref "C11") (pin "2") (pinfunction "2_2") (pintype "passive"))
      (node (ref "C12") (pin "2") (pinfunction "2_2") (pintype "passive"))
      (node (ref "C13") (pin "2") (pinfunction "2_2") (pintype "passive"))
      (node (ref "C14") (pin "2") (pinfunction "2_2") (pintype "passive"))
      (node (ref "C15") (pin "2") (pinfunction "2_2") (pintype "passive"))
      (node (ref "C16") (pin "1") (pinfunction "1_1") (pintype "passive"))
      (node (ref "C19") (pin "1") (pinfunction "1_1") (pintype "passive"))
      (node (ref "C2") (pin "2") (pinfunction "2_2") (pintype "passive"))
      (node (ref "C20") (pin "1") (pinfunction "1_1") (pintype "passive"))
      (node (ref "C21") (pin "2") (pinfunction "2_2") (pintype "passive"))
      (node (ref "C22") (pin "2") (pinfunction "2_2") (pintype "passive"))
      (node (ref "C23") (pin "1") (pinfunction "1_1") (pintype "passive"))
      (node (ref "C3") (pin "2") (pinfunction "2_2") (pintype "passive"))
      (node (ref "C4") (pin "2") (pinfunction "2_2") (pintype "passive"))
      (node (ref "C5") (pin "2") (pinfunction "2_2") (pintype "passive"))
      (node (ref "C6") (pin "2") (pinfunction "2_2") (pintype "passive"))
      (node (ref "C7") (pin "1") (pinfunction "1_1") (pintype "passive"))
      (node (ref "C8") (pin "2") (pinfunction "2_2") (pintype "passive"))
      (node (ref "C9") (pin "2") (pinfunction "2_2") (pintype "passive"))
      (node (ref "H1") (pin "1") (pinfunction "1_1") (pintype "passive"))
      (node (ref "H10") (pin "2") (pinfunction "2_2") (pintype "passive"))
      (node (ref "H11") (pin "2") (pinfunction "2_2") (pintype "passive"))
      (node (ref "H12") (pin "2") (pinfunction "2_2") (pintype "passive"))
      (node (ref "H13") (pin "2") (pinfunction "2_2") (pintype "passive"))
      (node (ref "H15") (pin "4") (pinfunction "4_4") (pintype "passive"))
      (node (ref "H16") (pin "1") (pinfunction "1_1") (pintype "passive"))
      (node (ref "H17") (pin "2") (pinfunction "2_2") (pintype "passive"))
      (node (ref "H17") (pin "3") (pinfunction "3_3") (pintype "passive"))
      (node (ref "H18") (pin "2") (pinfunction "2_2") (pintype "passive"))
      (node (ref "H18") (pin "3") (pinfunction "3_3") (pintype "passive"))
      (node (ref "H2") (pin "7") (pinfunction "7_7") (pintype "passive"))
      (node (ref "H2") (pin "8") (pinfunction "8_8") (pintype "passive"))
      (node (ref "H3") (pin "1") (pinfunction "1_1") (pintype "passive"))
      (node (ref "H4") (pin "1") (pinfunction "1_1") (pintype "passive"))
      (node (ref "H5") (pin "1") (pinfunction "1_1") (pintype "passive"))
      (node (ref "H9") (pin "1") (pinfunction "1_1") (pintype "passive"))
      (node (ref "K1") (pin "8") (pinfunction "8_8") (pintype "passive"))
      (node (ref "K2") (pin "8") (pinfunction "8_8") (pintype "passive"))
      (node (ref "L2") (pin "2") (pinfunction "2_2") (pintype "passive"))
      (node (ref "Q1") (pin "2") (pinfunction "2_2") (pintype "passive"))
      (node (ref "Q2") (pin "2") (pinfunction "2_2") (pintype "passive"))
      (node (ref "Q3") (pin "2") (pinfunction "2_2") (pintype "passive"))
      (node (ref "Q5") (pin "2") (pinfunction "2_2") (pintype "passive"))
      (node (ref "R10") (pin "2") (pinfunction "2_2") (pintype "passive"))
      (node (ref "R11") (pin "2") (pinfunction "2_2") (pintype "passive"))
      (node (ref "R12") (pin "2") (pinfunction "2_2") (pintype "passive"))
      (node (ref "R13") (pin "2") (pinfunction "2_2") (pintype "passive"))
      (node (ref "R14") (pin "2") (pinfunction "2_2") (pintype "passive"))
      (node (ref "R15") (pin "2") (pinfunction "2_2") (pintype "passive"))
      (node (ref "R17") (pin "2") (pinfunction "2_2") (pintype "passive"))
      (node (ref "R19") (pin "2") (pinfunction "2_2") (pintype "passive"))
      (node (ref "R28") (pin "1") (pinfunction "1_1") (pintype "passive"))
      (node (ref "R29") (pin "1") (pinfunction "1_1") (pintype "passive"))
      (node (ref "R34") (pin "1") (pinfunction "1_1") (pintype "passive"))
      (node (ref "R36") (pin "1") (pinfunction "1_1") (pintype "passive"))
      (node (ref "R40") (pin "1") (pinfunction "1_1") (pintype "passive"))
      (node (ref "R8") (pin "2") (pinfunction "2_2") (pintype "passive"))
      (node (ref "R9") (pin "2") (pinfunction "2_2") (pintype "passive"))
      (node (ref "U1") (pin "11") (pinfunction "GND_11") (pintype "passive"))
      (node (ref "U2") (pin "23") (pinfunction "VSS_23") (pintype "passive"))
      (node (ref "U2") (pin "47") (pinfunction "VSS_47") (pintype "passive"))
      (node (ref "U2") (pin "8") (pinfunction "VSSA_8") (pintype "passive"))
      (node (ref "U3") (pin "1") (pinfunction "GND_1") (pintype "passive"))
      (node (ref "U4") (pin "1") (pinfunction "GND_1") (pintype "passive"))
      (node (ref "U6") (pin "15") (pinfunction "GND_15") (pintype "passive"))
      (node (ref "U7") (pin "29") (pinfunction "EP_29") (pintype "passive"))
      (node (ref "U7") (pin "3") (pinfunction "GND_3") (pintype "passive"))
      (node (ref "U8") (pin "2") (pinfunction "GND_2") (pintype "power_in"))
      (node (ref "USB Host1") (pin "4") (pinfunction "GND_4") (pintype "passive"))
      (node (ref "X1") (pin "2") (pinfunction "2_2") (pintype "passive"))
      (node (ref "X1") (pin "4") (pinfunction "4_4") (pintype "passive"))
    )
    (net (code "59") (name "Net-(D1-A)") (class "Default")
      (node (ref "D1") (pin "2") (pinfunction "A_2") (pintype "passive"))
      (node (ref "H1") (pin "2") (pinfunction "2_2") (pintype "passive"))
    )
    (net (code "60") (name "Net-(D2-Pad2)") (class "Default")
      (node (ref "D2") (pin "2") (pinfunction "2_2") (pintype "passive"))
      (node (ref "D3") (pin "2") (pinfunction "2_2") (pintype "passive"))
      (node (ref "K1") (pin "10") (pinfunction "10_10") (pintype "passive"))
      (node (ref "Q1") (pin "3") (pinfunction "3_3") (pintype "passive"))
    )
    (net (code "61") (name "Net-(D3-Pad1)") (class "Default")
      (node (ref "D3") (pin "1") (pinfunction "1_1") (pintype "passive"))
      (node (ref "R22") (pin "1") (pinfunction "1_1") (pintype "passive"))
    )
    (net (code "62") (name "Net-(D4-Pad2)") (class "Default")
      (node (ref "D4") (pin "2") (pinfunction "2_2") (pintype "passive"))
      (node (ref "D5") (pin "2") (pinfunction "2_2") (pintype "passive"))
      (node (ref "K2") (pin "10") (pinfunction "10_10") (pintype "passive"))
      (node (ref "Q2") (pin "3") (pinfunction "3_3") (pintype "passive"))
    )
    (net (code "63") (name "Net-(D5-Pad1)") (class "Default")
      (node (ref "D5") (pin "1") (pinfunction "1_1") (pintype "passive"))
      (node (ref "R31") (pin "1") (pinfunction "1_1") (pintype "passive"))
    )
    (net (code "64") (name "Net-(D6-Pad2)") (class "Default")
      (node (ref "D6") (pin "2") (pinfunction "2_2") (pintype "passive"))
      (node (ref "D7") (pin "2") (pinfunction "2_2") (pintype "passive"))
      (node (ref "K3") (pin "10") (pinfunction "10_10") (pintype "passive"))
      (node (ref "Q3") (pin "3") (pinfunction "3_3") (pintype "passive"))
    )
    (net (code "65") (name "Net-(D7-Pad1)") (class "Default")
      (node (ref "D7") (pin "1") (pinfunction "1_1") (pintype "passive"))
      (node (ref "R32") (pin "1") (pinfunction "1_1") (pintype "passive"))
    )
    (net (code "66") (name "Net-(H15-Pad1)") (class "Default")
      (node (ref "H15") (pin "1") (pinfunction "1_1") (pintype "passive"))
      (node (ref "R24") (pin "1") (pinfunction "1_1") (pintype "passive"))
    )
    (net (code "67") (name "Net-(Q1-Pad1)") (class "Default")
      (node (ref "Q1") (pin "1") (pinfunction "1_1") (pintype "passive"))
      (node (ref "R27") (pin "1") (pinfunction "1_1") (pintype "passive"))
      (node (ref "R28") (pin "2") (pinfunction "2_2") (pintype "passive"))
    )
    (net (code "68") (name "Net-(Q2-Pad1)") (class "Default")
      (node (ref "Q2") (pin "1") (pinfunction "1_1") (pintype "passive"))
      (node (ref "R33") (pin "1") (pinfunction "1_1") (pintype "passive"))
      (node (ref "R34") (pin "2") (pinfunction "2_2") (pintype "passive"))
    )
    (net (code "69") (name "Net-(Q3-Pad1)") (class "Default")
      (node (ref "Q3") (pin "1") (pinfunction "1_1") (pintype "passive"))
      (node (ref "R35") (pin "1") (pinfunction "1_1") (pintype "passive"))
      (node (ref "R36") (pin "2") (pinfunction "2_2") (pintype "passive"))
    )
    (net (code "70") (name "Net-(Q4-GATE)") (class "Default")
      (node (ref "Q4") (pin "G") (pinfunction "GATE_G") (pintype "passive"))
      (node (ref "R37") (pin "2") (pinfunction "2_2") (pintype "passive"))
      (node (ref "R38") (pin "1") (pinfunction "1_1") (pintype "passive"))
    )
    (net (code "71") (name "Net-(Q5-Pad1)") (class "Default")
      (node (ref "Q5") (pin "1") (pinfunction "1_1") (pintype "passive"))
      (node (ref "R39") (pin "1") (pinfunction "1_1") (pintype "passive"))
      (node (ref "R40") (pin "2") (pinfunction "2_2") (pintype "passive"))
    )
    (net (code "72") (name "Net-(Q5-Pad3)") (class "Default")
      (node (ref "Q5") (pin "3") (pinfunction "3_3") (pintype "passive"))
      (node (ref "R38") (pin "2") (pinfunction "2_2") (pintype "passive"))
    )
    (net (code "73") (name "Net-(U2A-BOOT0)") (class "Default")
      (node (ref "R17") (pin "1") (pinfunction "1_1") (pintype "passive"))
      (node (ref "U2") (pin "44") (pinfunction "BOOT0_44") (pintype "passive"))
    )
    (net (code "74") (name "Net-(U2A-NRST)") (class "Default")
      (node (ref "C10") (pin "1") (pinfunction "1_1") (pintype "passive"))
      (node (ref "R16") (pin "2") (pinfunction "2_2") (pintype "passive"))
      (node (ref "U2") (pin "7") (pinfunction "NRST_7") (pintype "passive"))
    )
    (net (code "75") (name "Net-(U2A-PB4)") (class "Default")
      (node (ref "R1") (pin "2") (pinfunction "2_2") (pintype "passive"))
      (node (ref "R8") (pin "1") (pinfunction "1_1") (pintype "passive"))
      (node (ref "U2") (pin "40") (pinfunction "PB4_40") (pintype "passive"))
    )
    (net (code "76") (name "Net-(U2A-PB5)") (class "Default")
      (node (ref "R2") (pin "2") (pinfunction "2_2") (pintype "passive"))
      (node (ref "R9") (pin "1") (pinfunction "1_1") (pintype "passive"))
      (node (ref "U2") (pin "41") (pinfunction "PB5_41") (pintype "passive"))
    )
    (net (code "77") (name "Net-(U2A-PB6)") (class "Default")
      (node (ref "R10") (pin "1") (pinfunction "1_1") (pintype "passive"))
      (node (ref "R3") (pin "2") (pinfunction "2_2") (pintype "passive"))
      (node (ref "U2") (pin "42") (pinfunction "PB6_42") (pintype "passive"))
    )
    (net (code "78") (name "Net-(U2B-VDDA)") (class "Default")
      (node (ref "C9") (pin "1") (pinfunction "1_1") (pintype "passive"))
      (node (ref "L1") (pin "1") (pinfunction "1_1") (pintype "passive"))
      (node (ref "U2") (pin "9") (pinfunction "VDDA_9") (pintype "passive"))
    )
    (net (code "79") (name "Net-(U5-GND)") (class "Default")
      (node (ref "R18") (pin "2") (pinfunction "2_2") (pintype "passive"))
      (node (ref "R19") (pin "1") (pinfunction "1_1") (pintype "passive"))
      (node (ref "U5") (pin "1") (pinfunction "GND_1") (pintype "passive"))
    )
    (net (code "80") (name "Net-(U6-C1+)") (class "Default")
      (node (ref "C17") (pin "2") (pinfunction "2_2") (pintype "passive"))
      (node (ref "U6") (pin "1") (pinfunction "C1+_1") (pintype "passive"))
    )
    (net (code "81") (name "Net-(U6-C1-)") (class "Default")
      (node (ref "C17") (pin "1") (pinfunction "1_1") (pintype "passive"))
      (node (ref "U6") (pin "3") (pinfunction "C1-_3") (pintype "passive"))
    )
    (net (code "82") (name "Net-(U6-C2+)") (class "Default")
      (node (ref "C18") (pin "1") (pinfunction "1_1") (pintype "passive"))
      (node (ref "U6") (pin "4") (pinfunction "C2+_4") (pintype "passive"))
    )
    (net (code "83") (name "Net-(U6-C2-)") (class "Default")
      (node (ref "C18") (pin "2") (pinfunction "2_2") (pintype "passive"))
      (node (ref "U6") (pin "5") (pinfunction "C2-_5") (pintype "passive"))
    )
    (net (code "84") (name "Net-(U6-V+)") (class "Default")
      (node (ref "C16") (pin "2") (pinfunction "2_2") (pintype "passive"))
      (node (ref "U6") (pin "2") (pinfunction "V+_2") (pintype "passive"))
    )
    (net (code "85") (name "Net-(U6-V-)") (class "Default")
      (node (ref "C19") (pin "2") (pinfunction "2_2") (pintype "passive"))
      (node (ref "U6") (pin "6") (pinfunction "V-_6") (pintype "passive"))
    )
    (net (code "86") (name "Net-(U7-RST#)") (class "Default")
      (node (ref "R30") (pin "2") (pinfunction "2_2") (pintype "passive"))
      (node (ref "U7") (pin "9") (pinfunction "RST#_9") (pintype "passive"))
    )
    (net (code "87") (name "Net-(U7-SUSPEND#)") (class "Default")
      (node (ref "R29") (pin "2") (pinfunction "2_2") (pintype "passive"))
      (node (ref "U7") (pin "11") (pinfunction "SUSPEND#_11") (pintype "passive"))
    )
    (net (code "88") (name "Net-(USB Host1-Shield)") (class "Default")
      (node (ref "L2") (pin "1") (pinfunction "1_1") (pintype "passive"))
      (node (ref "USB Host1") (pin "Shell") (pinfunction "Shield_Shell") (pintype "passive"))
    )
    (net (code "89") (name "TTL-3V3") (class "Default")
      (node (ref "Q4") (pin "D") (pinfunction "DRAIN_D") (pintype "passive"))
      (node (ref "R25") (pin "2") (pinfunction "2_2") (pintype "passive"))
    )
    (net (code "90") (name "USB_5V") (class "Default")
      (node (ref "C21") (pin "1") (pinfunction "1_1") (pintype "passive"))
      (node (ref "C22") (pin "1") (pinfunction "1_1") (pintype "passive"))
      (node (ref "U7") (pin "7") (pinfunction "REGIN_7") (pintype "passive"))
      (node (ref "U7") (pin "8") (pinfunction "VBUS_8") (pintype "passive"))
      (node (ref "U8") (pin "5") (pinfunction "VBUS_5") (pintype "power_in"))
      (node (ref "USB Host1") (pin "1") (pinfunction "VBUS_1") (pintype "passive"))
    )
    (net (code "91") (name "VCC-3V3") (class "Default")
      (node (ref "C15") (pin "1") (pinfunction "1_1") (pintype "passive"))
      (node (ref "C20") (pin "2") (pinfunction "2_2") (pintype "passive"))
      (node (ref "C23") (pin "2") (pinfunction "2_2") (pintype "passive"))
      (node (ref "C5") (pin "1") (pinfunction "1_1") (pintype "passive"))
      (node (ref "C6") (pin "1") (pinfunction "1_1") (pintype "passive"))
      (node (ref "C7") (pin "2") (pinfunction "2_2") (pintype "passive"))
      (node (ref "C8") (pin "1") (pinfunction "1_1") (pintype "passive"))
      (node (ref "H2") (pin "5") (pinfunction "5_5") (pintype "passive"))
      (node (ref "H2") (pin "6") (pinfunction "6_6") (pintype "passive"))
      (node (ref "H9") (pin "4") (pinfunction "4_4") (pintype "passive"))
      (node (ref "L1") (pin "2") (pinfunction "2_2") (pintype "passive"))
      (node (ref "Q4") (pin "S") (pinfunction "SOURCE_S") (pintype "passive"))
      (node (ref "R1") (pin "1") (pinfunction "1_1") (pintype "passive"))
      (node (ref "R16") (pin "1") (pinfunction "1_1") (pintype "passive"))
      (node (ref "R2") (pin "1") (pinfunction "1_1") (pintype "passive"))
      (node (ref "R24") (pin "2") (pinfunction "2_2") (pintype "passive"))
      (node (ref "R3") (pin "1") (pinfunction "1_1") (pintype "passive"))
      (node (ref "R30") (pin "1") (pinfunction "1_1") (pintype "passive"))
      (node (ref "R37") (pin "1") (pinfunction "1_1") (pintype "passive"))
      (node (ref "U1") (pin "2") (pinfunction "VCCA_2") (pintype "passive"))
      (node (ref "U2") (pin "1") (pinfunction "VDD_1") (pintype "passive"))
      (node (ref "U2") (pin "24") (pinfunction "VDD_24") (pintype "passive"))
      (node (ref "U2") (pin "48") (pinfunction "VDD_48") (pintype "passive"))
      (node (ref "U4") (pin "2") (pinfunction "VOUT_2") (pintype "passive"))
      (node (ref "U4") (pin "4") (pinfunction "VOUT_4") (pintype "passive"))
      (node (ref "U6") (pin "16") (pinfunction "VCC_16") (pintype "passive"))
      (node (ref "U7") (pin "6") (pinfunction "VDD_6") (pintype "passive"))
    )
    (net (code "92") (name "VCC-4V2") (class "Default")
      (node (ref "C14") (pin "1") (pinfunction "1_1") (pintype "passive"))
      (node (ref "H2") (pin "3") (pinfunction "3_3") (pintype "passive"))
      (node (ref "H2") (pin "4") (pinfunction "4_4") (pintype "passive"))
      (node (ref "K2") (pin "3") (pinfunction "3_3") (pintype "passive"))
      (node (ref "R18") (pin "1") (pinfunction "1_1") (pintype "passive"))
      (node (ref "U5") (pin "2") (pinfunction "VOUT_2") (pintype "passive"))
      (node (ref "U5") (pin "4") (pinfunction "VOUT_4") (pintype "passive"))
    )
    (net (code "93") (name "VCC-5V") (class "Default")
      (node (ref "C3") (pin "1") (pinfunction "1_1") (pintype "passive"))
      (node (ref "D2") (pin "1") (pinfunction "1_1") (pintype "passive"))
      (node (ref "D4") (pin "1") (pinfunction "1_1") (pintype "passive"))
      (node (ref "D6") (pin "1") (pinfunction "1_1") (pintype "passive"))
      (node (ref "H2") (pin "1") (pinfunction "1_1") (pintype "passive"))
      (node (ref "H2") (pin "2") (pinfunction "2_2") (pintype "passive"))
      (node (ref "H3") (pin "4") (pinfunction "4_4") (pintype "passive"))
      (node (ref "K1") (pin "1") (pinfunction "1_1") (pintype "passive"))
      (node (ref "K1") (pin "3") (pinfunction "3_3") (pintype "passive"))
      (node (ref "K2") (pin "1") (pinfunction "1_1") (pintype "passive"))
      (node (ref "K3") (pin "1") (pinfunction "1_1") (pintype "passive"))
      (node (ref "R22") (pin "2") (pinfunction "2_2") (pintype "passive"))
      (node (ref "R31") (pin "2") (pinfunction "2_2") (pintype "passive"))
      (node (ref "R32") (pin "2") (pinfunction "2_2") (pintype "passive"))
      (node (ref "U1") (pin "19") (pinfunction "VCCB_19") (pintype "passive"))
      (node (ref "U3") (pin "2") (pinfunction "VOUT_2") (pintype "passive"))
      (node (ref "U3") (pin "4") (pinfunction "VOUT_4") (pintype "passive"))
    )
    (net (code "94") (name "unconnected-(K1-Pad2)") (class "Default")
      (node (ref "K1") (pin "2") (pinfunction "2_2") (pintype "passive+no_connect"))
    )
    (net (code "95") (name "unconnected-(K1-Pad5)") (class "Default")
      (node (ref "K1") (pin "5") (pinfunction "5_5") (pintype "passive+no_connect"))
    )
    (net (code "96") (name "unconnected-(K1-Pad6)") (class "Default")
      (node (ref "K1") (pin "6") (pinfunction "6_6") (pintype "passive+no_connect"))
    )
    (net (code "97") (name "unconnected-(K1-Pad9)") (class "Default")
      (node (ref "K1") (pin "9") (pinfunction "9_9") (pintype "passive+no_connect"))
    )
    (net (code "98") (name "unconnected-(K2-Pad2)") (class "Default")
      (node (ref "K2") (pin "2") (pinfunction "2_2") (pintype "passive+no_connect"))
    )
    (net (code "99") (name "unconnected-(K2-Pad5)") (class "Default")
      (node (ref "K2") (pin "5") (pinfunction "5_5") (pintype "passive+no_connect"))
    )
    (net (code "100") (name "unconnected-(K2-Pad6)") (class "Default")
      (node (ref "K2") (pin "6") (pinfunction "6_6") (pintype "passive+no_connect"))
    )
    (net (code "101") (name "unconnected-(K2-Pad9)") (class "Default")
      (node (ref "K2") (pin "9") (pinfunction "9_9") (pintype "passive+no_connect"))
    )
    (net (code "102") (name "unconnected-(K3-Pad2)") (class "Default")
      (node (ref "K3") (pin "2") (pinfunction "2_2") (pintype "passive+no_connect"))
    )
    (net (code "103") (name "unconnected-(K3-Pad5)") (class "Default")
      (node (ref "K3") (pin "5") (pinfunction "5_5") (pintype "passive+no_connect"))
    )
    (net (code "104") (name "unconnected-(K3-Pad6)") (class "Default")
      (node (ref "K3") (pin "6") (pinfunction "6_6") (pintype "passive+no_connect"))
    )
    (net (code "105") (name "unconnected-(K3-Pad9)") (class "Default")
      (node (ref "K3") (pin "9") (pinfunction "9_9") (pintype "passive+no_connect"))
    )
    (net (code "106") (name "unconnected-(U2A-PA11-Pad32)") (class "Default")
      (node (ref "U2") (pin "32") (pinfunction "PA11_32") (pintype "passive+no_connect"))
    )
    (net (code "107") (name "unconnected-(U2A-PA12-Pad33)") (class "Default")
      (node (ref "U2") (pin "33") (pinfunction "PA12_33") (pintype "passive+no_connect"))
    )
    (net (code "108") (name "unconnected-(U2A-PA15-Pad38)") (class "Default")
      (node (ref "U2") (pin "38") (pinfunction "PA15_38") (pintype "passive+no_connect"))
    )
    (net (code "109") (name "unconnected-(U2A-PB3-Pad39)") (class "Default")
      (node (ref "U2") (pin "39") (pinfunction "PB3_39") (pintype "passive+no_connect"))
    )
    (net (code "110") (name "unconnected-(U2A-PB7-Pad43)") (class "Default")
      (node (ref "U2") (pin "43") (pinfunction "PB7_43") (pintype "passive+no_connect"))
    )
    (net (code "111") (name "unconnected-(U2A-PB8-Pad45)") (class "Default")
      (node (ref "U2") (pin "45") (pinfunction "PB8_45") (pintype "passive+no_connect"))
    )
    (net (code "112") (name "unconnected-(U2A-PB9-Pad46)") (class "Default")
      (node (ref "U2") (pin "46") (pinfunction "PB9_46") (pintype "passive+no_connect"))
    )
    (net (code "113") (name "unconnected-(U2A-PB11-Pad22)") (class "Default")
      (node (ref "U2") (pin "22") (pinfunction "PB11_22") (pintype "passive+no_connect"))
    )
    (net (code "114") (name "unconnected-(U2A-PC13-Pad2)") (class "Default")
      (node (ref "U2") (pin "2") (pinfunction "PC13_2") (pintype "passive+no_connect"))
    )
    (net (code "115") (name "unconnected-(U2A-PC14-OSC32_IN(PC14)-Pad3)") (class "Default")
      (node (ref "U2") (pin "3") (pinfunction "PC14-OSC32_IN(PC14)_3") (pintype "passive+no_connect"))
    )
    (net (code "116") (name "unconnected-(U2A-PC15-OSC32_OUT(PC15)-Pad4)") (class "Default")
      (node (ref "U2") (pin "4") (pinfunction "PC15-OSC32_OUT(PC15)_4") (pintype "passive+no_connect"))
    )
    (net (code "117") (name "unconnected-(U2A-PF6-Pad35)") (class "Default")
      (node (ref "U2") (pin "35") (pinfunction "PF6_35") (pintype "passive+no_connect"))
    )
    (net (code "118") (name "unconnected-(U2A-PF7-Pad36)") (class "Default")
      (node (ref "U2") (pin "36") (pinfunction "PF7_36") (pintype "passive+no_connect"))
    )
    (net (code "119") (name "unconnected-(U6-R1IN-Pad13)") (class "Default")
      (node (ref "U6") (pin "13") (pinfunction "R1IN_13") (pintype "passive+no_connect"))
    )
    (net (code "120") (name "unconnected-(U6-R1OUT-Pad12)") (class "Default")
      (node (ref "U6") (pin "12") (pinfunction "R1OUT_12") (pintype "passive+no_connect"))
    )
    (net (code "121") (name "unconnected-(U6-T1IN-Pad11)") (class "Default")
      (node (ref "U6") (pin "11") (pinfunction "T1IN_11") (pintype "passive+no_connect"))
    )
    (net (code "122") (name "unconnected-(U6-T1OUT-Pad14)") (class "Default")
      (node (ref "U6") (pin "14") (pinfunction "T1OUT_14") (pintype "passive+no_connect"))
    )
    (net (code "123") (name "unconnected-(U7-CTS-Pad23)") (class "Default")
      (node (ref "U7") (pin "23") (pinfunction "CTS_23") (pintype "passive+no_connect"))
    )
    (net (code "124") (name "unconnected-(U7-DCD-Pad1)") (class "Default")
      (node (ref "U7") (pin "1") (pinfunction "DCD_1") (pintype "passive+no_connect"))
    )
    (net (code "125") (name "unconnected-(U7-DSR-Pad27)") (class "Default")
      (node (ref "U7") (pin "27") (pinfunction "DSR_27") (pintype "passive+no_connect"))
    )
    (net (code "126") (name "unconnected-(U7-DTR-Pad28)") (class "Default")
      (node (ref "U7") (pin "28") (pinfunction "DTR_28") (pintype "passive+no_connect"))
    )
    (net (code "127") (name "unconnected-(U7-NC-Pad10)") (class "Default")
      (node (ref "U7") (pin "10") (pinfunction "NC_10") (pintype "passive+no_connect"))
    )
    (net (code "128") (name "unconnected-(U7-NC-Pad13)") (class "Default")
      (node (ref "U7") (pin "13") (pinfunction "NC_13") (pintype "passive+no_connect"))
    )
    (net (code "129") (name "unconnected-(U7-NC-Pad14)") (class "Default")
      (node (ref "U7") (pin "14") (pinfunction "NC_14") (pintype "passive+no_connect"))
    )
    (net (code "130") (name "unconnected-(U7-NC-Pad15)") (class "Default")
      (node (ref "U7") (pin "15") (pinfunction "NC_15") (pintype "passive+no_connect"))
    )
    (net (code "131") (name "unconnected-(U7-NC-Pad16)") (class "Default")
      (node (ref "U7") (pin "16") (pinfunction "NC_16") (pintype "passive+no_connect"))
    )
    (net (code "132") (name "unconnected-(U7-NC-Pad17)") (class "Default")
      (node (ref "U7") (pin "17") (pinfunction "NC_17") (pintype "passive+no_connect"))
    )
    (net (code "133") (name "unconnected-(U7-NC-Pad18)") (class "Default")
      (node (ref "U7") (pin "18") (pinfunction "NC_18") (pintype "passive+no_connect"))
    )
    (net (code "134") (name "unconnected-(U7-NC-Pad19)") (class "Default")
      (node (ref "U7") (pin "19") (pinfunction "NC_19") (pintype "passive+no_connect"))
    )
    (net (code "135") (name "unconnected-(U7-NC-Pad20)") (class "Default")
      (node (ref "U7") (pin "20") (pinfunction "NC_20") (pintype "passive+no_connect"))
    )
    (net (code "136") (name "unconnected-(U7-NC-Pad21)") (class "Default")
      (node (ref "U7") (pin "21") (pinfunction "NC_21") (pintype "passive+no_connect"))
    )
    (net (code "137") (name "unconnected-(U7-NC-Pad22)") (class "Default")
      (node (ref "U7") (pin "22") (pinfunction "NC_22") (pintype "passive+no_connect"))
    )
    (net (code "138") (name "unconnected-(U7-RI-Pad2)") (class "Default")
      (node (ref "U7") (pin "2") (pinfunction "RI_2") (pintype "passive+no_connect"))
    )
    (net (code "139") (name "unconnected-(U7-RTS-Pad24)") (class "Default")
      (node (ref "U7") (pin "24") (pinfunction "RTS_24") (pintype "passive+no_connect"))
    )
    (net (code "140") (name "unconnected-(U7-SUSPEND-Pad12)") (class "Default")
      (node (ref "U7") (pin "12") (pinfunction "SUSPEND_12") (pintype "passive+no_connect"))
    )
  )
)
